# ENERGY.net
KiCad netlist of a schematic drawn in Altium Designer
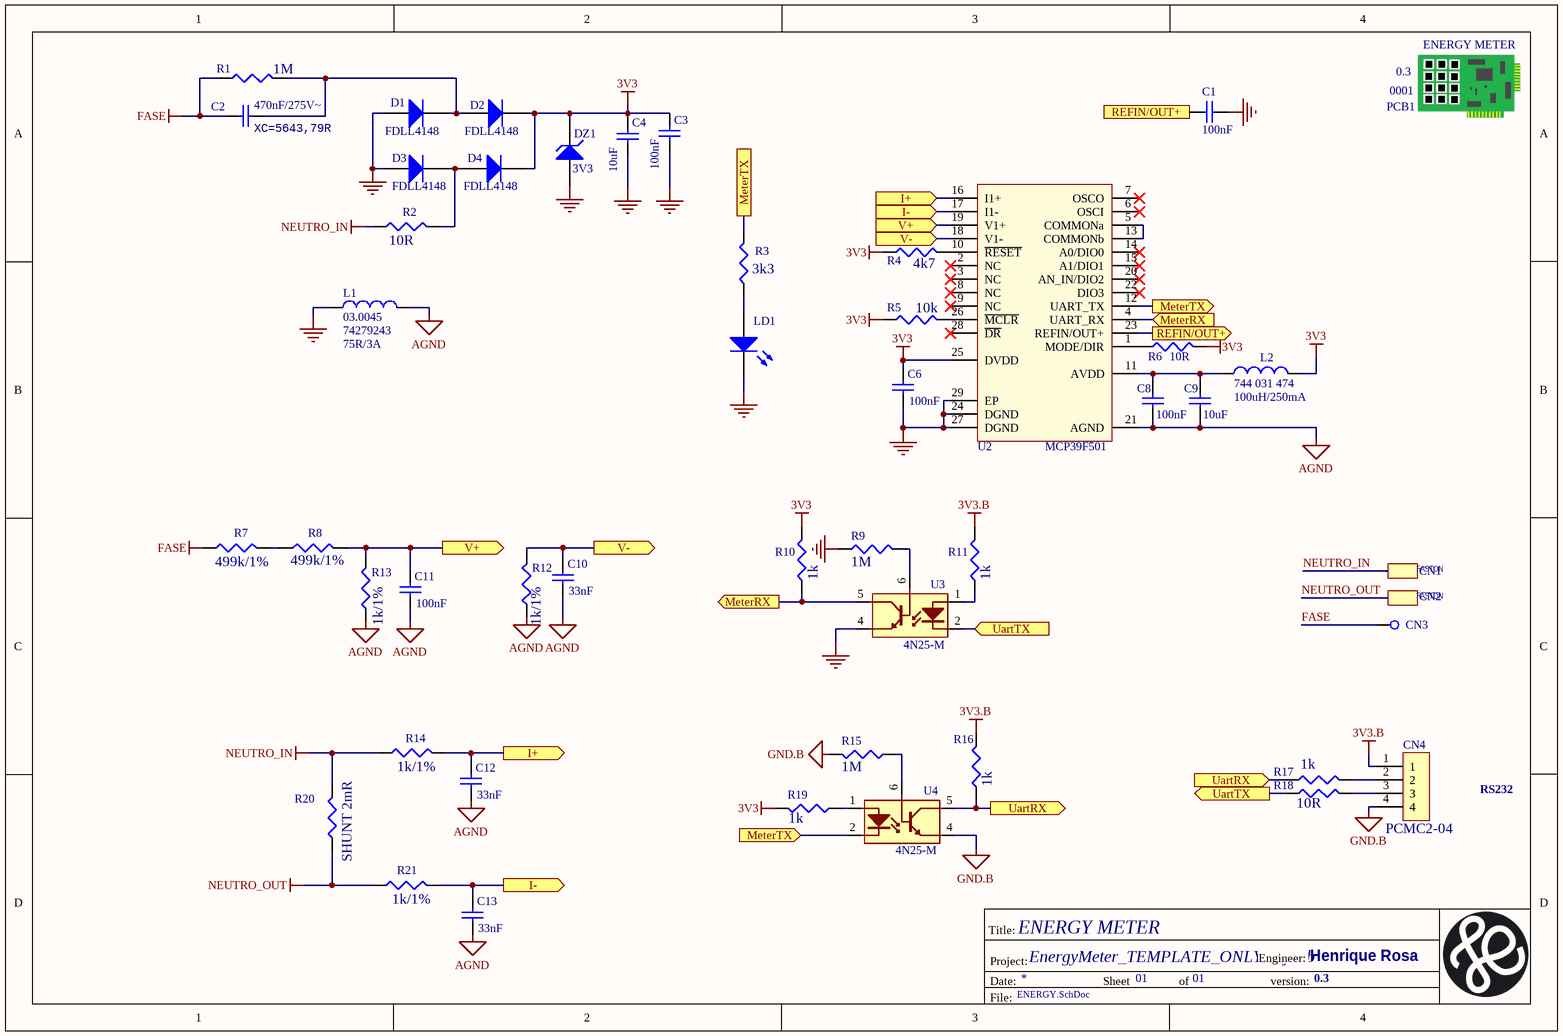
[diagram p0: ENERGY.SchDoc]

(export (version "E")
  (design (tool "Eeschema 10.0.6"))
  (components
    (comp (ref "C1")
      (value "Capacitor Cerâmico SMD")
      (footprint "0603 - CAP - montagem na maquina")
      (fields (field (name "VALOR") "100nF"))
      (libsource (lib "Miscellaneous Devices") (part "Capacitor Cerâmico SMD"))
    )
    (comp (ref "C2")
      (value "02.0032")
      (footprint "cap 470nF / 275V~")
      (description "Capacitor de Poliéster - MKP")
      (fields (field (name "VALOR") "470nF/275V~"))
      (libsource (lib "Miscellaneous Devices") (part "cap 220nF / 400V"))
    )
    (comp (ref "C3")
      (value "Capacitor Cerâmico SMD")
      (footprint "0603 - CAP - montagem na maquina")
      (fields (field (name "VALOR") "100nF"))
      (libsource (lib "Miscellaneous Devices") (part "Capacitor Cerâmico SMD"))
    )
    (comp (ref "C4")
      (value "Capacitor Cerâmico SMD")
      (footprint "0603 - CAP - montagem na maquina")
      (fields (field (name "VALOR") "10uF"))
      (libsource (lib "Miscellaneous Devices") (part "Capacitor Cerâmico SMD"))
    )
    (comp (ref "C6")
      (value "Capacitor Cerâmico SMD")
      (footprint "0603 - CAP - montagem na maquina")
      (fields (field (name "VALOR") "100nF"))
      (libsource (lib "Miscellaneous Devices") (part "Capacitor Cerâmico SMD"))
    )
    (comp (ref "C8")
      (value "Capacitor Cerâmico SMD")
      (footprint "0603 - CAP - montagem na maquina")
      (fields (field (name "VALOR") "100nF"))
      (libsource (lib "Miscellaneous Devices") (part "Capacitor Cerâmico SMD"))
    )
    (comp (ref "C9")
      (value "Capacitor Cerâmico SMD")
      (footprint "0805(cap)")
      (fields (field (name "VALOR") "10uF"))
      (libsource (lib "Miscellaneous Devices") (part "Capacitor Cerâmico SMD"))
    )
    (comp (ref "C10")
      (value "Capacitor Cerâmico SMD")
      (footprint "0603 - CAP - montagem na maquina")
      (fields (field (name "VALOR") "33nF"))
      (libsource (lib "Miscellaneous Devices") (part "Capacitor Cerâmico SMD"))
    )
    (comp (ref "C11")
      (value "Capacitor Cerâmico SMD")
      (footprint "0603 - CAP - montagem na maquina")
      (fields (field (name "VALOR") "100nF"))
      (libsource (lib "Miscellaneous Devices") (part "Capacitor Cerâmico SMD"))
    )
    (comp (ref "C12")
      (value "Capacitor Cerâmico SMD")
      (footprint "0603 - CAP - montagem na maquina")
      (fields (field (name "VALOR") "33nF"))
      (libsource (lib "Miscellaneous Devices") (part "Capacitor Cerâmico SMD"))
    )
    (comp (ref "C13")
      (value "Capacitor Cerâmico SMD")
      (footprint "0603 - CAP - montagem na maquina")
      (fields (field (name "VALOR") "33nF"))
      (libsource (lib "Miscellaneous Devices") (part "Capacitor Cerâmico SMD"))
    )
    (comp (ref "CN1")
      (value "5mm")
      (footprint "FASTON FEMALE 180G")
      (description "Faston Fêmea 90graus")
      (libsource (lib "Miscellaneous Connectors") (part "FASTON FEMEA 180G"))
    )
    (comp (ref "CN2")
      (value "5mm")
      (footprint "FASTON FEMALE 180G")
      (description "Faston Fêmea 90graus")
      (libsource (lib "Miscellaneous Connectors") (part "FASTON FEMEA 180G"))
    )
    (comp (ref "CN3")
      (value "##nl")
      (footprint "Testpoint-1mm")
      (description "Testpoint")
      (libsource (lib "Miscellaneous Devices") (part "TESTPOINT"))
    )
    (comp (ref "CN4")
      (value "11.0417")
      (footprint "PCMC2-04")
      (description "Conector header")
      (fields (field (name "PART NUMBER") "PCMC2-04"))
      (libsource (lib "METALTEX") (part "PCMC2-04"))
    )
    (comp (ref "D1")
      (value "Diode")
      (footprint "DIODE_SMD_2mm")
      (description "Default Diode")
      (fields (field (name "PART NUMBER") "FDLL4148"))
      (libsource (lib "Miscellaneous Devices") (part "Diode"))
    )
    (comp (ref "D2")
      (value "Diode")
      (footprint "DIODE_SMD_2mm")
      (description "Default Diode")
      (fields (field (name "PART NUMBER") "FDLL4148"))
      (libsource (lib "Miscellaneous Devices") (part "Diode"))
    )
    (comp (ref "D3")
      (value "Diode")
      (footprint "DIODE_SMD_2mm")
      (description "Default Diode")
      (fields (field (name "PART NUMBER") "FDLL4148"))
      (libsource (lib "Miscellaneous Devices") (part "Diode"))
    )
    (comp (ref "D4")
      (value "Diode")
      (footprint "DIODE_SMD_2mm")
      (description "Default Diode")
      (fields (field (name "PART NUMBER") "FDLL4148"))
      (libsource (lib "Miscellaneous Devices") (part "Diode"))
    )
    (comp (ref "DZ1")
      (value "3V3")
      (footprint "DIODE_SMD_2mm")
      (description "Zener Diode")
      (fields (field (name "PART NUMBER") "MMSZ5231B"))
      (libsource (lib "Miscellaneous Devices") (part "Diode Zener"))
    )
    (comp (ref "L1")
      (value "03.0045")
      (footprint "1806 ind WURTH")
      (description "Indutor")
      (fields (field (name "PART NUMBER") "74279243") (field (name "VALOR") "75R/3A"))
      (libsource (lib "WHURT_INDUTORES") (part "742 792 43"))
    )
    (comp (ref "L2")
      (value "03.0105")
      (footprint "744031100")
      (description "Indutor")
      (fields (field (name "PART NUMBER") "744 031 474") (field (name "VALOR") "100uH/250mA"))
      (libsource (lib "WHURT_INDUTORES") (part "744 031 101"))
    )
    (comp (ref "LD1")
      (value "LED2")
      (footprint "LED 0805")
      (description "Led")
      (libsource (lib "Miscellaneous Devices") (part "LED2"))
    )
    (comp (ref "PCB1")
      (value "0001")
      (description "=ProjectName")
      (fields (field (name "REV") "0.3") (field (name "VALOR") "ENERGY METER"))
      (libsource (lib "PCI") (part "PCI"))
    )
    (comp (ref "R1")
      (value "Res3")
      (footprint "0603 - MONTAGEM MÁQUINA")
      (description "Resistor")
      (fields (field (name "VALOR") "1M"))
      (libsource (lib "Miscellaneous Devices") (part "Res3"))
    )
    (comp (ref "R2")
      (value "Res3")
      (footprint "0603 - MONTAGEM MÁQUINA")
      (description "Resistor")
      (fields (field (name "VALOR") "10R"))
      (libsource (lib "Miscellaneous Devices") (part "Res3"))
    )
    (comp (ref "R3")
      (value "Res3")
      (footprint "0603 - MONTAGEM MÁQUINA")
      (description "Resistor")
      (fields (field (name "VALOR") "3k3"))
      (libsource (lib "Miscellaneous Devices") (part "Res3"))
    )
    (comp (ref "R4")
      (value "Res3")
      (footprint "0603 - MONTAGEM MÁQUINA")
      (description "Resistor")
      (fields (field (name "VALOR") "4k7"))
      (libsource (lib "Miscellaneous Devices") (part "Res3"))
    )
    (comp (ref "R5")
      (value "Res3")
      (footprint "0603 - MONTAGEM MÁQUINA")
      (description "Resistor")
      (fields (field (name "VALOR") "10k"))
      (libsource (lib "Miscellaneous Devices") (part "Res3"))
    )
    (comp (ref "R6")
      (value "Res3")
      (footprint "0603 - MONTAGEM MÁQUINA")
      (description "Resistor")
      (fields (field (name "VALOR") "10R"))
      (libsource (lib "Miscellaneous Devices") (part "Res3"))
    )
    (comp (ref "R7")
      (value "Res3")
      (footprint "0603 - MONTAGEM MÁQUINA")
      (description "Resistor")
      (fields (field (name "VALOR") "499k/1%"))
      (libsource (lib "Miscellaneous Devices") (part "Res3"))
    )
    (comp (ref "R8")
      (value "Res3")
      (footprint "0603 - MONTAGEM MÁQUINA")
      (description "Resistor")
      (fields (field (name "VALOR") "499k/1%"))
      (libsource (lib "Miscellaneous Devices") (part "Res3"))
    )
    (comp (ref "R9")
      (value "Res3")
      (footprint "0603 - MONTAGEM MÁQUINA")
      (description "Resistor")
      (fields (field (name "VALOR") "1M"))
      (libsource (lib "Miscellaneous Devices") (part "Res3"))
    )
    (comp (ref "R10")
      (value "Res3")
      (footprint "0603 - MONTAGEM MÁQUINA")
      (description "Resistor")
      (fields (field (name "VALOR") "1k"))
      (libsource (lib "Miscellaneous Devices") (part "Res3"))
    )
    (comp (ref "R11")
      (value "Res3")
      (footprint "0603 - MONTAGEM MÁQUINA")
      (description "Resistor")
      (fields (field (name "VALOR") "1k"))
      (libsource (lib "Miscellaneous Devices") (part "Res3"))
    )
    (comp (ref "R12")
      (value "Res3")
      (footprint "0603 - MONTAGEM MÁQUINA")
      (description "Resistor")
      (fields (field (name "VALOR") "1k/1%"))
      (libsource (lib "Miscellaneous Devices") (part "Res3"))
    )
    (comp (ref "R13")
      (value "Res3")
      (footprint "0603 - MONTAGEM MÁQUINA")
      (description "Resistor")
      (fields (field (name "VALOR") "1k/1%"))
      (libsource (lib "Miscellaneous Devices") (part "Res3"))
    )
    (comp (ref "R14")
      (value "Res3")
      (footprint "0603 - MONTAGEM MÁQUINA")
      (description "Resistor")
      (fields (field (name "VALOR") "1k/1%"))
      (libsource (lib "Miscellaneous Devices") (part "Res3"))
    )
    (comp (ref "R15")
      (value "Res3")
      (footprint "0603 - MONTAGEM MÁQUINA")
      (description "Resistor")
      (fields (field (name "VALOR") "1M"))
      (libsource (lib "Miscellaneous Devices") (part "Res3"))
    )
    (comp (ref "R16")
      (value "Res3")
      (footprint "0603 - MONTAGEM MÁQUINA")
      (description "Resistor")
      (fields (field (name "VALOR") "1k"))
      (libsource (lib "Miscellaneous Devices") (part "Res3"))
    )
    (comp (ref "R17")
      (value "Res3")
      (footprint "0603 - MONTAGEM MÁQUINA")
      (description "Resistor")
      (fields (field (name "VALOR") "1k"))
      (libsource (lib "Miscellaneous Devices") (part "Res3"))
    )
    (comp (ref "R18")
      (value "Res3")
      (footprint "0603 - MONTAGEM MÁQUINA")
      (description "Resistor")
      (fields (field (name "VALOR") "10R"))
      (libsource (lib "Miscellaneous Devices") (part "Res3"))
    )
    (comp (ref "R19")
      (value "Res3")
      (footprint "0603 - MONTAGEM MÁQUINA")
      (description "Resistor")
      (fields (field (name "VALOR") "1k"))
      (libsource (lib "Miscellaneous Devices") (part "Res3"))
    )
    (comp (ref "R20")
      (value "Res3")
      (footprint "2512")
      (description "Resistor")
      (fields (field (name "VALOR") "SHUNT 2mR"))
      (libsource (lib "Miscellaneous Devices") (part "Res3"))
    )
    (comp (ref "R21")
      (value "Res3")
      (footprint "0603 - MONTAGEM MÁQUINA")
      (description "Resistor")
      (fields (field (name "VALOR") "1k/1%"))
      (libsource (lib "Miscellaneous Devices") (part "Res3"))
    )
    (comp (ref "U2")
      (value "07.1140")
      (footprint "QFN 5x5")
      (description "Energy Meter")
      (fields (field (name "PART NUMBER") "MCP39F501"))
      (libsource (lib "MICROCHIP") (part "MCP39F501"))
    )
    (comp (ref "U3")
      (value "07.0195")
      (footprint "DIP 6 BRANCO M SUFFIX")
      (description "Optoacoplador(Branco)")
      (fields (field (name "PART NUMBER") "4N25-M"))
      (libsource (lib "") (part "OPTO 4N25-M_1"))
    )
    (comp (ref "U4")
      (value "07.0195")
      (footprint "DIP 6 BRANCO M SUFFIX")
      (description "Optoacoplador(Branco)")
      (fields (field (name "PART NUMBER") "4N25-M"))
      (libsource (lib "Miscellaneous Devices") (part "OPTO 4N25-M"))
    )
  )
  (nets
    (net (code "1") (name "/I+") (class "Default")
      (node (ref "C12") (pin "2") (pinfunction "2_2") (pintype "passive"))
      (node (ref "R14") (pin "2") (pinfunction "2_2") (pintype "passive"))
      (node (ref "U2") (pin "16") (pinfunction "I1+_16") (pintype "passive"))
    )
    (net (code "2") (name "/I-") (class "Default")
      (node (ref "C13") (pin "2") (pinfunction "2_2") (pintype "passive"))
      (node (ref "R21") (pin "2") (pinfunction "2_2") (pintype "passive"))
      (node (ref "U2") (pin "17") (pinfunction "I1-_17") (pintype "passive"))
    )
    (net (code "3") (name "/MeterRX") (class "Default")
      (node (ref "R10") (pin "2") (pinfunction "2_2") (pintype "passive"))
      (node (ref "U2") (pin "4") (pinfunction "UART_RX_4") (pintype "passive"))
      (node (ref "U3") (pin "5") (pinfunction "C_5") (pintype "passive"))
    )
    (net (code "4") (name "/MeterTX") (class "Default")
      (node (ref "R3") (pin "2") (pinfunction "2_2") (pintype "passive"))
      (node (ref "U2") (pin "12") (pinfunction "UART_TX_12") (pintype "passive"))
      (node (ref "U4") (pin "2") (pinfunction "K_2") (pintype "passive"))
    )
    (net (code "5") (name "/REFIN{slash}OUT+") (class "Default")
      (node (ref "C1") (pin "2") (pinfunction "2_2") (pintype "passive"))
      (node (ref "U2") (pin "23") (pinfunction "REFIN/OUT+_23") (pintype "passive"))
    )
    (net (code "6") (name "/UartRX") (class "Default")
      (node (ref "R16") (pin "2") (pinfunction "2_2") (pintype "passive"))
      (node (ref "R17") (pin "2") (pinfunction "2_2") (pintype "passive"))
      (node (ref "U4") (pin "5") (pinfunction "C_5") (pintype "passive"))
    )
    (net (code "7") (name "/UartTX") (class "Default")
      (node (ref "R18") (pin "2") (pinfunction "2_2") (pintype "passive"))
      (node (ref "U3") (pin "2") (pinfunction "K_2") (pintype "passive"))
    )
    (net (code "8") (name "/V+") (class "Default")
      (node (ref "C11") (pin "2") (pinfunction "2_2") (pintype "passive"))
      (node (ref "R13") (pin "2") (pinfunction "2_2") (pintype "passive"))
      (node (ref "R8") (pin "2") (pinfunction "2_2") (pintype "passive"))
      (node (ref "U2") (pin "19") (pinfunction "V1+_19") (pintype "passive"))
    )
    (net (code "9") (name "/V-") (class "Default")
      (node (ref "C10") (pin "2") (pinfunction "2_2") (pintype "passive"))
      (node (ref "R12") (pin "2") (pinfunction "2_2") (pintype "passive"))
      (node (ref "U2") (pin "18") (pinfunction "V1-_18") (pintype "passive"))
    )
    (net (code "10") (name "3V3") (class "Default")
      (node (ref "C3") (pin "2") (pinfunction "2_2") (pintype "passive"))
      (node (ref "C4") (pin "2") (pinfunction "2_2") (pintype "passive"))
      (node (ref "C6") (pin "2") (pinfunction "2_2") (pintype "passive"))
      (node (ref "D2") (pin "2") (pinfunction "K_2") (pintype "passive"))
      (node (ref "D4") (pin "2") (pinfunction "K_2") (pintype "passive"))
      (node (ref "DZ1") (pin "2") (pinfunction "K_2") (pintype "passive"))
      (node (ref "L2") (pin "2") (pinfunction "2_2") (pintype "passive"))
      (node (ref "R10") (pin "1") (pinfunction "1_1") (pintype "passive"))
      (node (ref "R19") (pin "1") (pinfunction "1_1") (pintype "passive"))
      (node (ref "R4") (pin "1") (pinfunction "1_1") (pintype "passive"))
      (node (ref "R5") (pin "1") (pinfunction "1_1") (pintype "passive"))
      (node (ref "R6") (pin "1") (pinfunction "1_1") (pintype "passive"))
      (node (ref "U2") (pin "25") (pinfunction "DVDD_25") (pintype "passive"))
    )
    (net (code "11") (name "3V3.B") (class "Default")
      (node (ref "CN4") (pin "1") (pinfunction "1_1") (pintype "passive"))
      (node (ref "R11") (pin "1") (pinfunction "1_1") (pintype "passive"))
      (node (ref "R16") (pin "1") (pinfunction "1_1") (pintype "passive"))
    )
    (net (code "12") (name "AGND") (class "Default")
      (node (ref "C10") (pin "1") (pinfunction "1_1") (pintype "passive"))
      (node (ref "C11") (pin "1") (pinfunction "1_1") (pintype "passive"))
      (node (ref "C12") (pin "1") (pinfunction "1_1") (pintype "passive"))
      (node (ref "C13") (pin "1") (pinfunction "1_1") (pintype "passive"))
      (node (ref "C8") (pin "1") (pinfunction "1_1") (pintype "passive"))
      (node (ref "C9") (pin "1") (pinfunction "1_1") (pintype "passive"))
      (node (ref "L1") (pin "2") (pinfunction "2_2") (pintype "passive"))
      (node (ref "R12") (pin "1") (pinfunction "1_1") (pintype "passive"))
      (node (ref "R13") (pin "1") (pinfunction "1_1") (pintype "passive"))
      (node (ref "U2") (pin "21") (pinfunction "AGND_21") (pintype "passive"))
    )
    (net (code "13") (name "EARTH") (class "Default")
      (node (ref "C1") (pin "1") (pinfunction "1_1") (pintype "passive"))
      (node (ref "C3") (pin "1") (pinfunction "1_1") (pintype "passive"))
      (node (ref "C4") (pin "1") (pinfunction "1_1") (pintype "passive"))
      (node (ref "C6") (pin "1") (pinfunction "1_1") (pintype "passive"))
      (node (ref "D1") (pin "1") (pinfunction "A_1") (pintype "passive"))
      (node (ref "D3") (pin "1") (pinfunction "A_1") (pintype "passive"))
      (node (ref "DZ1") (pin "1") (pinfunction "A_1") (pintype "passive"))
      (node (ref "L1") (pin "1") (pinfunction "1_1") (pintype "passive"))
      (node (ref "LD1") (pin "2") (pinfunction "K_2") (pintype "passive"))
      (node (ref "R9") (pin "2") (pinfunction "2_2") (pintype "passive"))
      (node (ref "U2") (pin "24") (pinfunction "DGND_24") (pintype "passive"))
      (node (ref "U2") (pin "27") (pinfunction "DGND_27") (pintype "passive"))
      (node (ref "U2") (pin "29") (pinfunction "EP_29") (pintype "passive"))
      (node (ref "U3") (pin "4") (pinfunction "E_4") (pintype "passive"))
    )
    (net (code "14") (name "FASE") (class "Default")
      (node (ref "C2") (pin "1") (pinfunction "1_1") (pintype "passive"))
      (node (ref "CN3") (pin "1") (pinfunction "1_1") (pintype "passive"))
      (node (ref "R1") (pin "1") (pinfunction "1_1") (pintype "passive"))
      (node (ref "R7") (pin "1") (pinfunction "1_1") (pintype "passive"))
    )
    (net (code "15") (name "GND.B") (class "Default")
      (node (ref "CN4") (pin "4") (pinfunction "4_4") (pintype "passive"))
      (node (ref "R15") (pin "1") (pinfunction "1_1") (pintype "passive"))
      (node (ref "U4") (pin "4") (pinfunction "E_4") (pintype "passive"))
    )
    (net (code "16") (name "NEUTRO_IN") (class "Default")
      (node (ref "CN1") (pin "1") (pinfunction "1_1") (pintype "passive"))
      (node (ref "R14") (pin "1") (pinfunction "1_1") (pintype "passive"))
      (node (ref "R2") (pin "1") (pinfunction "1_1") (pintype "passive"))
      (node (ref "R20") (pin "2") (pinfunction "2_2") (pintype "passive"))
    )
    (net (code "17") (name "NEUTRO_OUT") (class "Default")
      (node (ref "CN2") (pin "1") (pinfunction "1_1") (pintype "passive"))
      (node (ref "R20") (pin "1") (pinfunction "1_1") (pintype "passive"))
      (node (ref "R21") (pin "1") (pinfunction "1_1") (pintype "passive"))
    )
    (net (code "18") (name "Net-(CN4-Pad2)") (class "Default")
      (node (ref "CN4") (pin "2") (pinfunction "2_2") (pintype "passive"))
      (node (ref "R17") (pin "1") (pinfunction "1_1") (pintype "passive"))
    )
    (net (code "19") (name "Net-(CN4-Pad3)") (class "Default")
      (node (ref "CN4") (pin "3") (pinfunction "3_3") (pintype "passive"))
      (node (ref "R18") (pin "1") (pinfunction "1_1") (pintype "passive"))
    )
    (net (code "20") (name "Net-(D1-K)") (class "Default")
      (node (ref "C2") (pin "2") (pinfunction "2_2") (pintype "passive"))
      (node (ref "D1") (pin "2") (pinfunction "K_2") (pintype "passive"))
      (node (ref "D2") (pin "1") (pinfunction "A_1") (pintype "passive"))
      (node (ref "R1") (pin "2") (pinfunction "2_2") (pintype "passive"))
    )
    (net (code "21") (name "Net-(D3-K)") (class "Default")
      (node (ref "D3") (pin "2") (pinfunction "K_2") (pintype "passive"))
      (node (ref "D4") (pin "1") (pinfunction "A_1") (pintype "passive"))
      (node (ref "R2") (pin "2") (pinfunction "2_2") (pintype "passive"))
    )
    (net (code "22") (name "Net-(LD1-A)") (class "Default")
      (node (ref "LD1") (pin "1") (pinfunction "A_1") (pintype "passive"))
      (node (ref "R3") (pin "1") (pinfunction "1_1") (pintype "passive"))
    )
    (net (code "23") (name "Net-(R7-Pad2)") (class "Default")
      (node (ref "R7") (pin "2") (pinfunction "2_2") (pintype "passive"))
      (node (ref "R8") (pin "1") (pinfunction "1_1") (pintype "passive"))
    )
    (net (code "24") (name "Net-(U2-AVDD)") (class "Default")
      (node (ref "C8") (pin "2") (pinfunction "2_2") (pintype "passive"))
      (node (ref "C9") (pin "2") (pinfunction "2_2") (pintype "passive"))
      (node (ref "L2") (pin "1") (pinfunction "1_1") (pintype "passive"))
      (node (ref "U2") (pin "11") (pinfunction "AVDD_11") (pintype "passive"))
    )
    (net (code "25") (name "Net-(U2-COMMONa)") (class "Default")
      (node (ref "U2") (pin "13") (pinfunction "COMMONb_13") (pintype "passive"))
      (node (ref "U2") (pin "5") (pinfunction "COMMONa_5") (pintype "passive"))
    )
    (net (code "26") (name "Net-(U2-MODE{slash}DIR)") (class "Default")
      (node (ref "R6") (pin "2") (pinfunction "2_2") (pintype "passive"))
      (node (ref "U2") (pin "1") (pinfunction "MODE/DIR_1") (pintype "passive"))
    )
    (net (code "27") (name "Net-(U2-~{MCLR})") (class "Default")
      (node (ref "R5") (pin "2") (pinfunction "2_2") (pintype "passive"))
      (node (ref "U2") (pin "26") (pinfunction "~{MCLR}_26") (pintype "passive"))
    )
    (net (code "28") (name "Net-(U2-~{RESET})") (class "Default")
      (node (ref "R4") (pin "2") (pinfunction "2_2") (pintype "passive"))
      (node (ref "U2") (pin "10") (pinfunction "~{RESET}_10") (pintype "passive"))
    )
    (net (code "29") (name "Net-(U3-A)") (class "Default")
      (node (ref "R11") (pin "2") (pinfunction "2_2") (pintype "passive"))
      (node (ref "U3") (pin "1") (pinfunction "A_1") (pintype "passive"))
    )
    (net (code "30") (name "Net-(U3-B)") (class "Default")
      (node (ref "R9") (pin "1") (pinfunction "1_1") (pintype "passive"))
      (node (ref "U3") (pin "6") (pinfunction "B_6") (pintype "passive"))
    )
    (net (code "31") (name "Net-(U4-A)") (class "Default")
      (node (ref "R19") (pin "2") (pinfunction "2_2") (pintype "passive"))
      (node (ref "U4") (pin "1") (pinfunction "A_1") (pintype "passive"))
    )
    (net (code "32") (name "Net-(U4-B)") (class "Default")
      (node (ref "R15") (pin "2") (pinfunction "2_2") (pintype "passive"))
      (node (ref "U4") (pin "6") (pinfunction "B_6") (pintype "passive"))
    )
    (net (code "33") (name "unconnected-(U2-A0{slash}DIO0-Pad14)") (class "Default")
      (node (ref "U2") (pin "14") (pinfunction "A0/DIO0_14") (pintype "passive+no_connect"))
    )
    (net (code "34") (name "unconnected-(U2-A1{slash}DIO1-Pad15)") (class "Default")
      (node (ref "U2") (pin "15") (pinfunction "A1/DIO1_15") (pintype "passive+no_connect"))
    )
    (net (code "35") (name "unconnected-(U2-AN_IN{slash}DIO2-Pad20)") (class "Default")
      (node (ref "U2") (pin "20") (pinfunction "AN_IN/DIO2_20") (pintype "passive+no_connect"))
    )
    (net (code "36") (name "unconnected-(U2-DIO3-Pad22)") (class "Default")
      (node (ref "U2") (pin "22") (pinfunction "DIO3_22") (pintype "passive+no_connect"))
    )
    (net (code "37") (name "unconnected-(U2-NC-Pad2)") (class "Default")
      (node (ref "U2") (pin "2") (pinfunction "NC_2") (pintype "passive+no_connect"))
    )
    (net (code "38") (name "unconnected-(U2-NC-Pad3)") (class "Default")
      (node (ref "U2") (pin "3") (pinfunction "NC_3") (pintype "passive+no_connect"))
    )
    (net (code "39") (name "unconnected-(U2-NC-Pad8)") (class "Default")
      (node (ref "U2") (pin "8") (pinfunction "NC_8") (pintype "passive+no_connect"))
    )
    (net (code "40") (name "unconnected-(U2-NC-Pad9)") (class "Default")
      (node (ref "U2") (pin "9") (pinfunction "NC_9") (pintype "passive+no_connect"))
    )
    (net (code "41") (name "unconnected-(U2-OSCI-Pad6)") (class "Default")
      (node (ref "U2") (pin "6") (pinfunction "OSCI_6") (pintype "passive+no_connect"))
    )
    (net (code "42") (name "unconnected-(U2-OSCO-Pad7)") (class "Default")
      (node (ref "U2") (pin "7") (pinfunction "OSCO_7") (pintype "passive+no_connect"))
    )
    (net (code "43") (name "unconnected-(U2-~{DR}-Pad28)") (class "Default")
      (node (ref "U2") (pin "28") (pinfunction "~{DR}_28") (pintype "passive+no_connect"))
    )
  )
)
